# rfm12-breakout.net
KiCad netlist of a schematic drawn in EAGLE
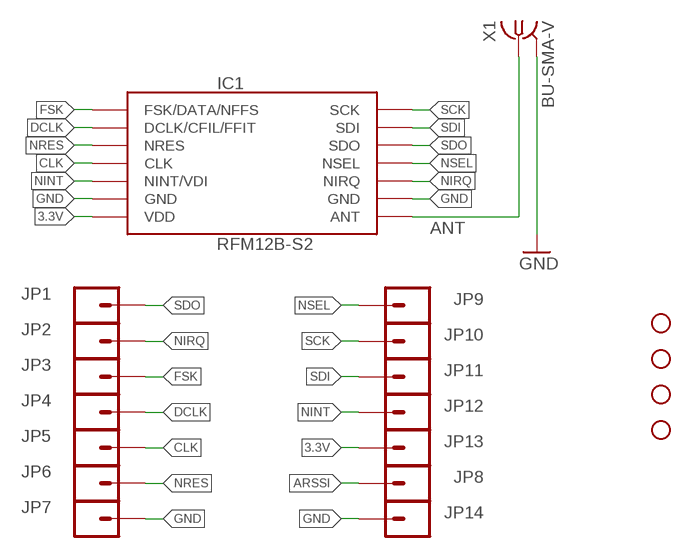
[diagram p0: schematic, sheet 1]

(export (version "E")
  (design (tool "Eeschema 10.0.6"))
  (components
    (comp (ref "IC1")
      (value "RFM12B-S2")
      (footprint "eagle-import:RFM12B-S2")
      (libsource (lib "eagle-import") (part "RFM12B-S2"))
    )
    (comp (ref "JP1")
      (value "M01")
      (footprint "eagle-import:1X01")
      (libsource (lib "eagle-import") (part "M01"))
    )
    (comp (ref "JP2")
      (value "M01")
      (footprint "eagle-import:1X01")
      (libsource (lib "eagle-import") (part "M01"))
    )
    (comp (ref "JP3")
      (value "M01")
      (footprint "eagle-import:1X01")
      (libsource (lib "eagle-import") (part "M01"))
    )
    (comp (ref "JP4")
      (value "M01")
      (footprint "eagle-import:1X01")
      (libsource (lib "eagle-import") (part "M01"))
    )
    (comp (ref "JP5")
      (value "M01")
      (footprint "eagle-import:1X01")
      (libsource (lib "eagle-import") (part "M01"))
    )
    (comp (ref "JP6")
      (value "M01")
      (footprint "eagle-import:1X01")
      (libsource (lib "eagle-import") (part "M01"))
    )
    (comp (ref "JP7")
      (value "M01")
      (footprint "eagle-import:1X01")
      (libsource (lib "eagle-import") (part "M01"))
    )
    (comp (ref "JP8")
      (value "M01")
      (footprint "eagle-import:1X01")
      (libsource (lib "eagle-import") (part "M01"))
    )
    (comp (ref "JP9")
      (value "M01")
      (footprint "eagle-import:1X01")
      (libsource (lib "eagle-import") (part "M01"))
    )
    (comp (ref "JP10")
      (value "M01")
      (footprint "eagle-import:1X01")
      (libsource (lib "eagle-import") (part "M01"))
    )
    (comp (ref "JP11")
      (value "M01")
      (footprint "eagle-import:1X01")
      (libsource (lib "eagle-import") (part "M01"))
    )
    (comp (ref "JP12")
      (value "M01")
      (footprint "eagle-import:1X01")
      (libsource (lib "eagle-import") (part "M01"))
    )
    (comp (ref "JP13")
      (value "M01")
      (footprint "eagle-import:1X01")
      (libsource (lib "eagle-import") (part "M01"))
    )
    (comp (ref "JP14")
      (value "M01")
      (footprint "eagle-import:1X01")
      (libsource (lib "eagle-import") (part "M01"))
    )
    (comp (ref "STANDOFF1")
      (value "STAND-OFF")
      (footprint "eagle-import:STAND-OFF")
      (libsource (lib "eagle-import") (part "STAND-OFF"))
    )
    (comp (ref "STANDOFF2")
      (value "STAND-OFF")
      (footprint "eagle-import:STAND-OFF")
      (libsource (lib "eagle-import") (part "STAND-OFF"))
    )
    (comp (ref "STANDOFF3")
      (value "STAND-OFF")
      (footprint "eagle-import:STAND-OFF")
      (libsource (lib "eagle-import") (part "STAND-OFF"))
    )
    (comp (ref "STANDOFF4")
      (value "STAND-OFF")
      (footprint "eagle-import:STAND-OFF")
      (libsource (lib "eagle-import") (part "STAND-OFF"))
    )
    (comp (ref "X1")
      (value "BU-SMA-V")
      (footprint "eagle-import:BU-SMA-V")
      (libsource (lib "eagle-import") (part "BU-SMA-V"))
    )
  )
  (nets
    (net (code "1") (name "/ANT") (class "Default")
      (node (ref "IC1") (pin "ANT") (pinfunction "ANT_ANT") (pintype "output"))
      (node (ref "X1") (pin "1") (pinfunction "1_1") (pintype "passive"))
    )
    (net (code "2") (name "3.3V") (class "Default")
      (node (ref "IC1") (pin "VDD") (pinfunction "VDD_VDD") (pintype "power_in"))
      (node (ref "JP13") (pin "1") (pinfunction "1_1") (pintype "passive"))
    )
    (net (code "3") (name "ARSSI") (class "Default")
      (node (ref "JP8") (pin "1") (pinfunction "1_1") (pintype "passive"))
    )
    (net (code "4") (name "CLK") (class "Default")
      (node (ref "IC1") (pin "CLK") (pinfunction "CLK_CLK") (pintype "output"))
      (node (ref "JP5") (pin "1") (pinfunction "1_1") (pintype "passive"))
    )
    (net (code "5") (name "DCLK") (class "Default")
      (node (ref "IC1") (pin "DCLK/CFIL/FFIT") (pinfunction "DCLK/CFIL/FFIT_DCLK/CFIL/FFIT") (pintype "bidirectional"))
      (node (ref "JP4") (pin "1") (pinfunction "1_1") (pintype "passive"))
    )
    (net (code "6") (name "FSK") (class "Default")
      (node (ref "IC1") (pin "FSK/DATA/NFFS") (pinfunction "FSK/DATA/NFFS_FSK/DATA/NFFS") (pintype "bidirectional"))
      (node (ref "JP3") (pin "1") (pinfunction "1_1") (pintype "passive"))
    )
    (net (code "7") (name "GND") (class "Default")
      (node (ref "IC1") (pin "GND@1") (pinfunction "GND_GND@1") (pintype "power_in"))
      (node (ref "IC1") (pin "GND@2") (pinfunction "GND_GND@2") (pintype "power_in"))
      (node (ref "JP14") (pin "1") (pinfunction "1_1") (pintype "passive"))
      (node (ref "JP7") (pin "1") (pinfunction "1_1") (pintype "passive"))
      (node (ref "X1") (pin "2") (pinfunction "2_2") (pintype "passive"))
      (node (ref "X1") (pin "3") (pinfunction "2_3") (pintype "passive"))
      (node (ref "X1") (pin "4") (pinfunction "2_4") (pintype "passive"))
      (node (ref "X1") (pin "5") (pinfunction "2_5") (pintype "passive"))
    )
    (net (code "8") (name "NINT") (class "Default")
      (node (ref "IC1") (pin "NINT/VDI") (pinfunction "NINT/VDI_NINT/VDI") (pintype "bidirectional"))
      (node (ref "JP12") (pin "1") (pinfunction "1_1") (pintype "passive"))
    )
    (net (code "9") (name "NIRQ") (class "Default")
      (node (ref "IC1") (pin "NIRQ") (pinfunction "NIRQ_NIRQ") (pintype "output"))
      (node (ref "JP2") (pin "1") (pinfunction "1_1") (pintype "passive"))
    )
    (net (code "10") (name "NRES") (class "Default")
      (node (ref "IC1") (pin "NRES") (pinfunction "NRES_NRES") (pintype "bidirectional"))
      (node (ref "JP6") (pin "1") (pinfunction "1_1") (pintype "passive"))
    )
    (net (code "11") (name "NSEL") (class "Default")
      (node (ref "IC1") (pin "NSEL") (pinfunction "NSEL_NSEL") (pintype "input"))
      (node (ref "JP9") (pin "1") (pinfunction "1_1") (pintype "passive"))
    )
    (net (code "12") (name "SCK") (class "Default")
      (node (ref "IC1") (pin "SCK") (pinfunction "SCK_SCK") (pintype "input"))
      (node (ref "JP10") (pin "1") (pinfunction "1_1") (pintype "passive"))
    )
    (net (code "13") (name "SDI") (class "Default")
      (node (ref "IC1") (pin "SDI") (pinfunction "SDI_SDI") (pintype "input"))
      (node (ref "JP11") (pin "1") (pinfunction "1_1") (pintype "passive"))
    )
    (net (code "14") (name "SDO") (class "Default")
      (node (ref "IC1") (pin "SDO") (pinfunction "SDO_SDO") (pintype "output"))
      (node (ref "JP1") (pin "1") (pinfunction "1_1") (pintype "passive"))
    )
  )
)
